# Astable_Multivibrator.net
KiCad netlist of a schematic drawn in EAGLE
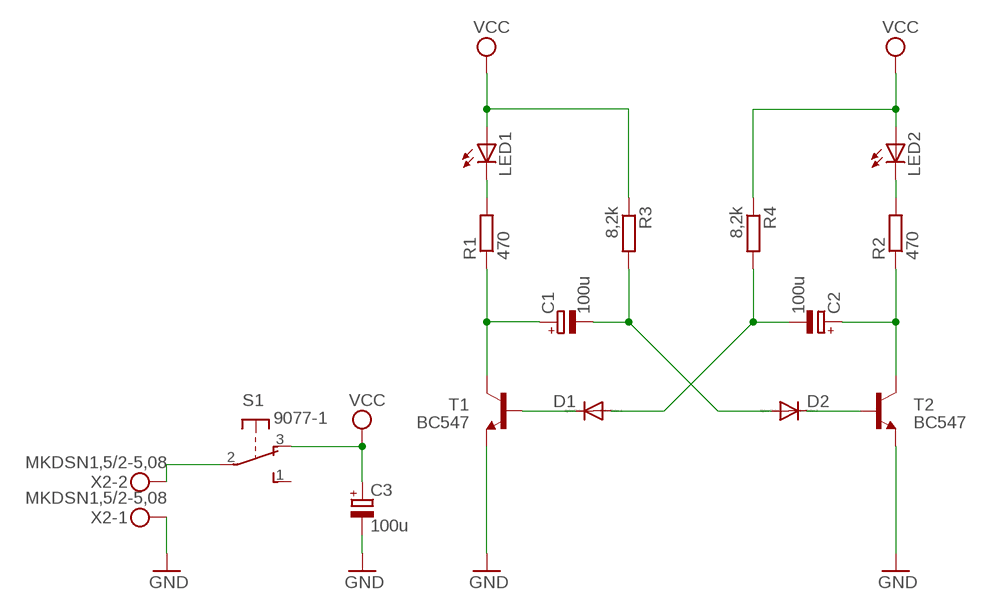
[diagram p0: schematic, sheet 1]

(export (version "E")
  (design (tool "Eeschema 10.0.6"))
  (components
    (comp (ref "C1")
      (value "100u")
      (footprint "eagle-import:E2,5-6")
      (libsource (lib "eagle-import") (part "CPOL-EUE2.5-6"))
    )
    (comp (ref "C2")
      (value "100u")
      (footprint "eagle-import:E2,5-6")
      (libsource (lib "eagle-import") (part "CPOL-EUE2.5-6"))
    )
    (comp (ref "C3")
      (value "100u")
      (footprint "eagle-import:E2,5-6")
      (libsource (lib "eagle-import") (part "CPOL-EUE2.5-6"))
    )
    (comp (ref "D1")
      (value "1N4148DO35-7")
      (footprint "eagle-import:DO35-7")
      (libsource (lib "eagle-import") (part "1N4148DO35-7"))
    )
    (comp (ref "D2")
      (value "1N4148DO35-7")
      (footprint "eagle-import:DO35-7")
      (libsource (lib "eagle-import") (part "1N4148DO35-7"))
    )
    (comp (ref "LED1")
      (value "LED5MM")
      (footprint "eagle-import:LED5MM")
      (libsource (lib "eagle-import") (part "LED5MM"))
    )
    (comp (ref "LED2")
      (value "LED5MM")
      (footprint "eagle-import:LED5MM")
      (libsource (lib "eagle-import") (part "LED5MM"))
    )
    (comp (ref "R1")
      (value "470")
      (footprint "eagle-import:0207_10")
      (libsource (lib "eagle-import") (part "R-EU_0207/10"))
    )
    (comp (ref "R2")
      (value "470")
      (footprint "eagle-import:0207_10")
      (libsource (lib "eagle-import") (part "R-EU_0207/10"))
    )
    (comp (ref "R3")
      (value "8,2k")
      (footprint "eagle-import:0207_10")
      (libsource (lib "eagle-import") (part "R-EU_0207/10"))
    )
    (comp (ref "R4")
      (value "8,2k")
      (footprint "eagle-import:0207_10")
      (libsource (lib "eagle-import") (part "R-EU_0207/10"))
    )
    (comp (ref "S1")
      (value "9077-1")
      (footprint "eagle-import:9077-1")
      (libsource (lib "eagle-import") (part "9077-1"))
    )
    (comp (ref "T1")
      (value "BC547")
      (footprint "eagle-import:TO92")
      (libsource (lib "eagle-import") (part "BC547B"))
    )
    (comp (ref "T2")
      (value "BC547")
      (footprint "eagle-import:TO92")
      (libsource (lib "eagle-import") (part "BC547B"))
    )
    (comp (ref "X2")
      (value "MKDSN1,5/2-5,08")
      (footprint "eagle-import:MKDSN1,5_2-5,08")
      (libsource (lib "eagle-import") (part "MKDSN1,5/2-5,08"))
    )
  )
  (nets
    (net (code "1") (name "GND") (class "Default")
      (node (ref "C3") (pin "-") (pinfunction "-_-") (pintype "passive"))
      (node (ref "T1") (pin "1") (pinfunction "E_1") (pintype "passive"))
      (node (ref "T2") (pin "1") (pinfunction "E_1") (pintype "passive"))
      (node (ref "X2") (pin "1") (pinfunction "KL_1") (pintype "passive"))
    )
    (net (code "2") (name "Net-(C1-Pad-)") (class "Default")
      (node (ref "C1") (pin "-") (pinfunction "-_-") (pintype "passive"))
      (node (ref "D2") (pin "A") (pinfunction "A_A") (pintype "passive"))
      (node (ref "R3") (pin "2") (pinfunction "2_2") (pintype "passive"))
    )
    (net (code "3") (name "Net-(C2-Pad-)") (class "Default")
      (node (ref "C2") (pin "-") (pinfunction "-_-") (pintype "passive"))
      (node (ref "D1") (pin "A") (pinfunction "A_A") (pintype "passive"))
      (node (ref "R4") (pin "2") (pinfunction "2_2") (pintype "passive"))
    )
    (net (code "4") (name "Net-(LED1-C)") (class "Default")
      (node (ref "LED1") (pin "K") (pinfunction "C_K") (pintype "passive"))
      (node (ref "R1") (pin "2") (pinfunction "2_2") (pintype "passive"))
    )
    (net (code "5") (name "Net-(LED2-C)") (class "Default")
      (node (ref "LED2") (pin "K") (pinfunction "C_K") (pintype "passive"))
      (node (ref "R2") (pin "2") (pinfunction "2_2") (pintype "passive"))
    )
    (net (code "6") (name "Net-(S1-P)") (class "Default")
      (node (ref "S1") (pin "2") (pinfunction "P_2") (pintype "passive"))
      (node (ref "X2") (pin "2") (pinfunction "KL_2") (pintype "passive"))
    )
    (net (code "7") (name "Net-(T1-B)") (class "Default")
      (node (ref "D1") (pin "C") (pinfunction "C_C") (pintype "passive"))
      (node (ref "T1") (pin "2") (pinfunction "B_2") (pintype "passive"))
    )
    (net (code "8") (name "Net-(T1-C)") (class "Default")
      (node (ref "C1") (pin "+") (pinfunction "+_+") (pintype "passive"))
      (node (ref "R1") (pin "1") (pinfunction "1_1") (pintype "passive"))
      (node (ref "T1") (pin "3") (pinfunction "C_3") (pintype "passive"))
    )
    (net (code "9") (name "Net-(T2-B)") (class "Default")
      (node (ref "D2") (pin "C") (pinfunction "C_C") (pintype "passive"))
      (node (ref "T2") (pin "2") (pinfunction "B_2") (pintype "passive"))
    )
    (net (code "10") (name "Net-(T2-C)") (class "Default")
      (node (ref "C2") (pin "+") (pinfunction "+_+") (pintype "passive"))
      (node (ref "R2") (pin "1") (pinfunction "1_1") (pintype "passive"))
      (node (ref "T2") (pin "3") (pinfunction "C_3") (pintype "passive"))
    )
    (net (code "11") (name "VCC") (class "Default")
      (node (ref "C3") (pin "+") (pinfunction "+_+") (pintype "passive"))
      (node (ref "LED1") (pin "A") (pinfunction "A_A") (pintype "passive"))
      (node (ref "LED2") (pin "A") (pinfunction "A_A") (pintype "passive"))
      (node (ref "R3") (pin "1") (pinfunction "1_1") (pintype "passive"))
      (node (ref "R4") (pin "1") (pinfunction "1_1") (pintype "passive"))
      (node (ref "S1") (pin "3") (pinfunction "O_3") (pintype "passive"))
    )
    (net (code "12") (name "unconnected-(S1-S-Pad1)") (class "Default")
      (node (ref "S1") (pin "1") (pinfunction "S_1") (pintype "passive"))
    )
  )
)
